# TSOC_MINIPROG_ADAPTER_R1_1.net
KiCad netlist of a schematic drawn in EAGLE
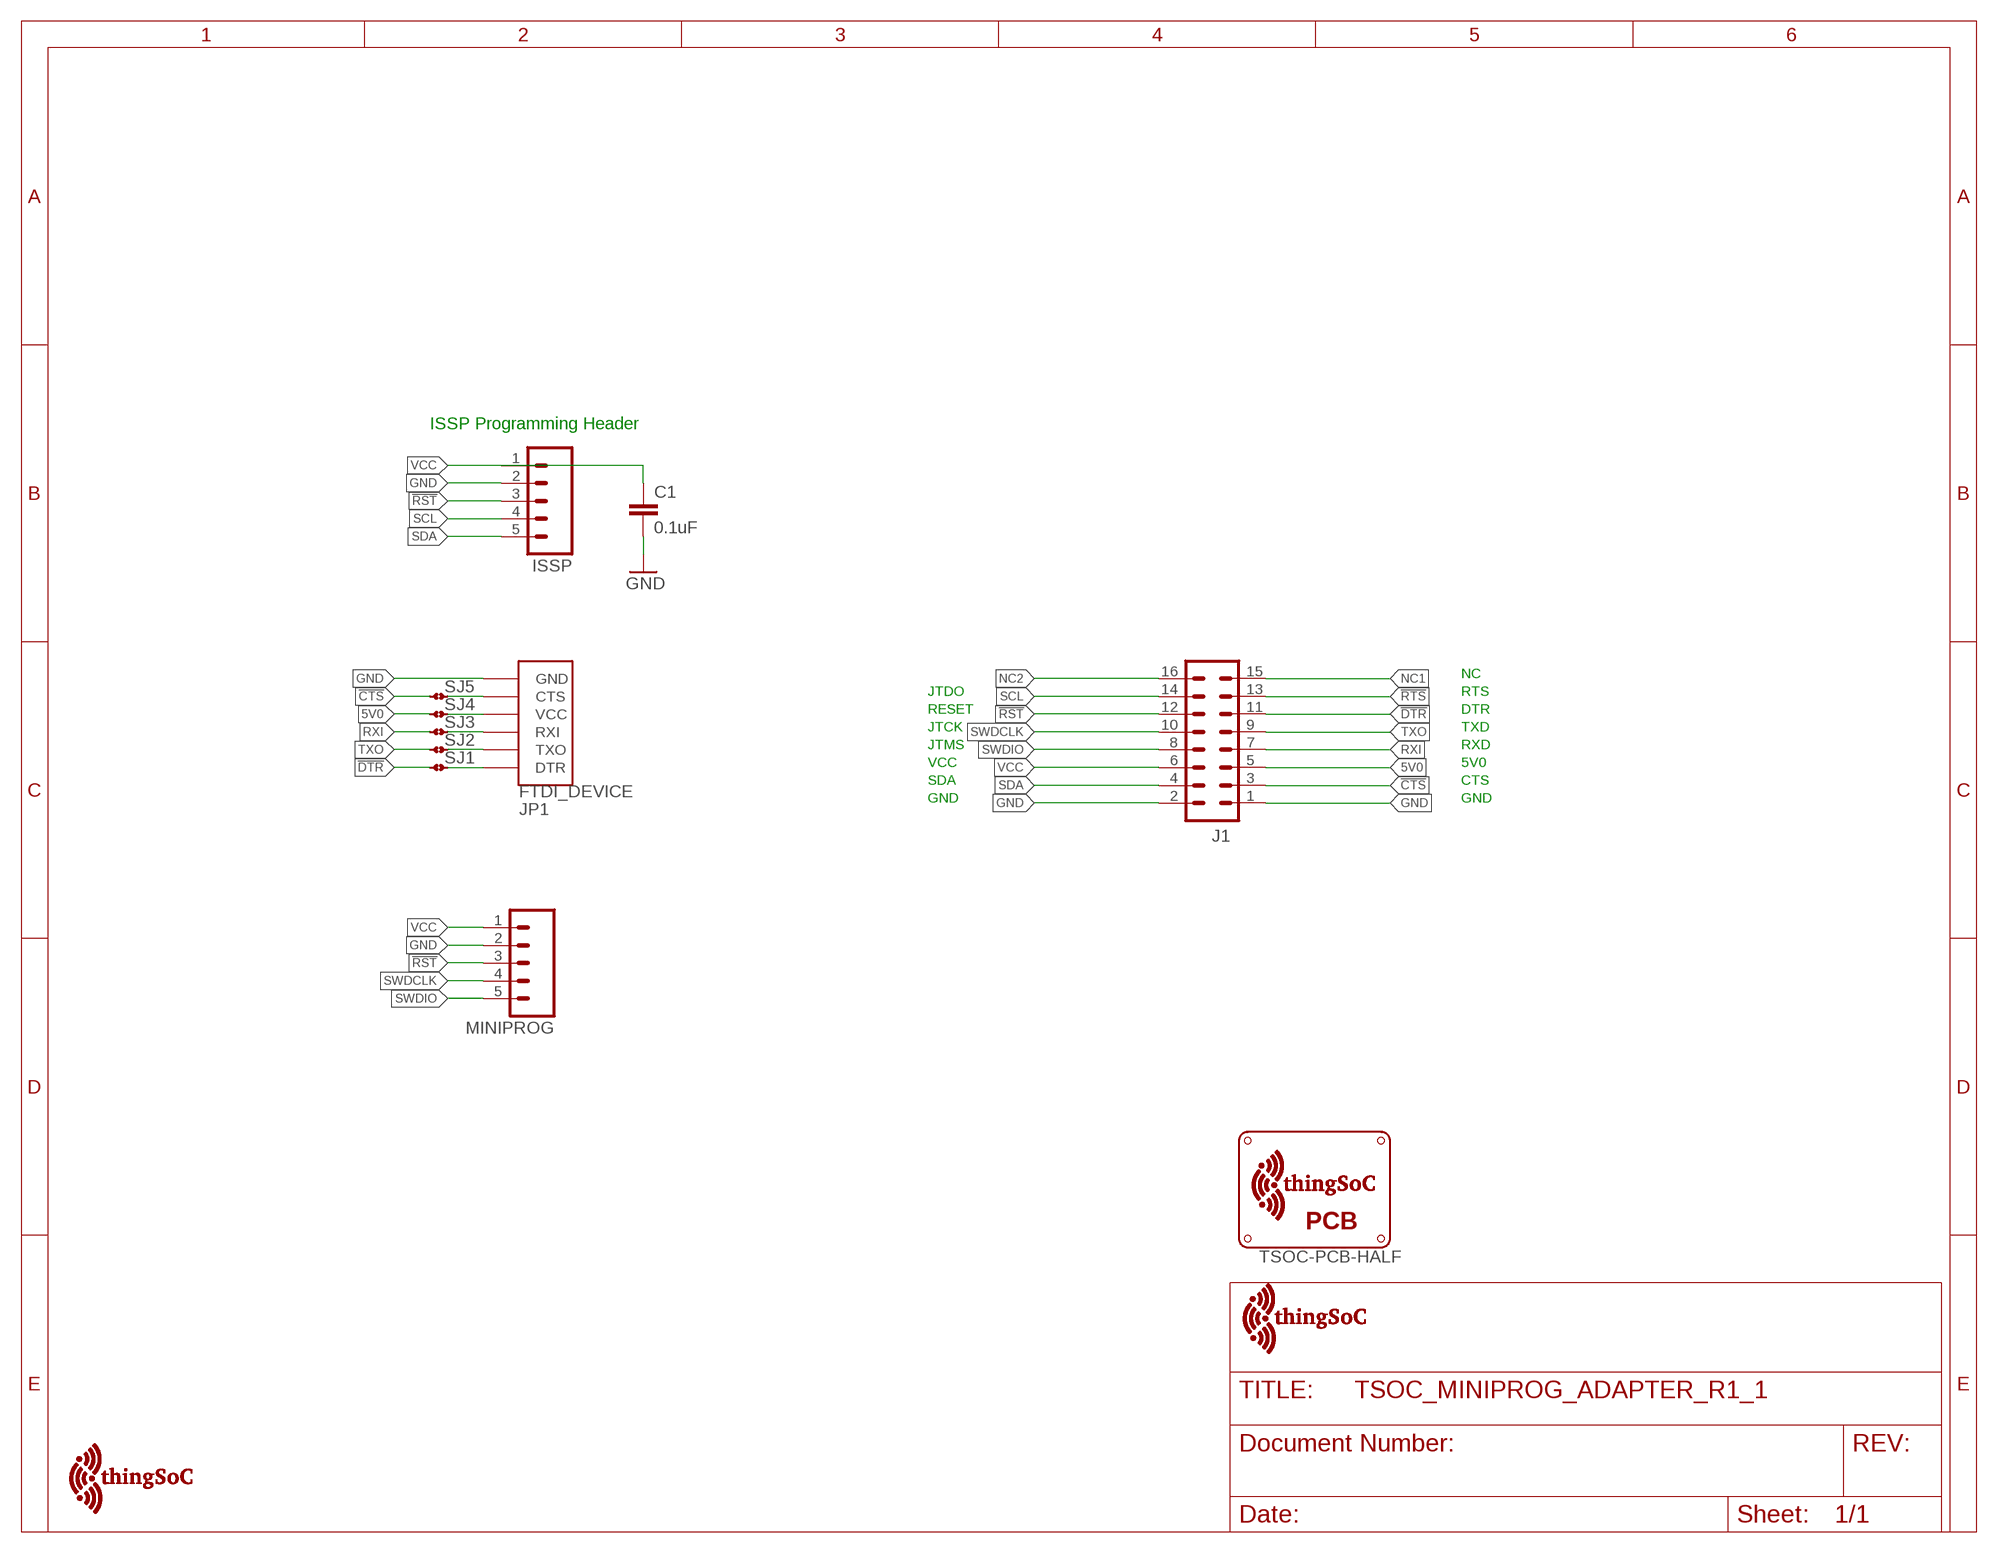
[diagram p0: schematic, sheet 1]

(export (version "E")
  (design (tool "Eeschema 10.0.6"))
  (components
    (comp (ref "C1")
      (value "0.1uF")
      (footprint "eagle-import:0603-CAP")
      (libsource (lib "eagle-import") (part "CAP0603-CAP"))
    )
    (comp (ref "ISSP")
      (value "M05PTH")
      (footprint "eagle-import:1X05")
      (libsource (lib "eagle-import") (part "M05PTH"))
    )
    (comp (ref "J1")
      (value "M08X2")
      (footprint "eagle-import:2X8")
      (libsource (lib "eagle-import") (part "M08X2"))
    )
    (comp (ref "JP1")
      (value "FTDI_DEVICE")
      (footprint "eagle-import:FTDI_DEVICE_SIDE")
      (libsource (lib "eagle-import") (part "FTDI_DEVICE"))
    )
    (comp (ref "MINIPROG")
      (value "M05PTH")
      (footprint "eagle-import:1X05")
      (libsource (lib "eagle-import") (part "SparkFun-Connectors_M05PTH"))
    )
    (comp (ref "SJ1")
      (value "JMP-2-NO")
      (footprint "eagle-import:JMP-2-NO")
      (libsource (lib "eagle-import") (part "JMP-2-NO"))
    )
    (comp (ref "SJ2")
      (value "JMP-2-NO")
      (footprint "eagle-import:JMP-2-NO")
      (libsource (lib "eagle-import") (part "JMP-2-NO"))
    )
    (comp (ref "SJ3")
      (value "JMP-2-NO")
      (footprint "eagle-import:JMP-2-NO")
      (libsource (lib "eagle-import") (part "JMP-2-NO"))
    )
    (comp (ref "SJ4")
      (value "JMP-2-NO")
      (footprint "eagle-import:JMP-2-NO")
      (libsource (lib "eagle-import") (part "JMP-2-NO"))
    )
    (comp (ref "SJ5")
      (value "JMP-2-NO")
      (footprint "eagle-import:JMP-2-NO")
      (libsource (lib "eagle-import") (part "JMP-2-NO"))
    )
    (comp (ref "U$3")
      (value "TSOC-LOGO-SMALL")
      (footprint "eagle-import:TSOC-LOGO-SML")
      (libsource (lib "eagle-import") (part "TSOC-LOGO-SMALL"))
    )
    (comp (ref "U$4")
      (value "TSOC-PCB-HALF")
      (footprint "eagle-import:TSOC-BB-BRD-HALF")
      (libsource (lib "eagle-import") (part "TSOC-PCB-HALF"))
    )
    (comp (ref "U$5")
      (value "TSOC-LOGO-SMALL")
      (footprint "eagle-import:TSOC-LOGO-SML")
      (libsource (lib "eagle-import") (part "TSOC-LOGO-SMALL"))
    )
    (comp (ref "U$6")
      (value "TSOC-LOGO-LRG")
      (footprint "eagle-import:TSOC-LOGO-LRG")
      (libsource (lib "eagle-import") (part "TSOC-LOGO-LRG"))
    )
  )
  (nets
    (net (code "1") (name "/~{CTS}") (class "Default")
      (node (ref "J1") (pin "3") (pinfunction "3_3") (pintype "passive"))
      (node (ref "SJ5") (pin "1") (pinfunction "1_1") (pintype "passive"))
    )
    (net (code "2") (name "/~{DTR}") (class "Default")
      (node (ref "J1") (pin "11") (pinfunction "11_11") (pintype "passive"))
      (node (ref "SJ1") (pin "1") (pinfunction "1_1") (pintype "passive"))
    )
    (net (code "3") (name "/~{RST}") (class "Default")
      (node (ref "ISSP") (pin "3") (pinfunction "3_3") (pintype "passive"))
      (node (ref "J1") (pin "12") (pinfunction "12_12") (pintype "passive"))
      (node (ref "MINIPROG") (pin "3") (pinfunction "3_3") (pintype "passive"))
    )
    (net (code "4") (name "/~{RTS}") (class "Default")
      (node (ref "J1") (pin "13") (pinfunction "13_13") (pintype "passive"))
    )
    (net (code "5") (name "5V0") (class "Default")
      (node (ref "J1") (pin "5") (pinfunction "5_5") (pintype "passive"))
      (node (ref "SJ4") (pin "1") (pinfunction "1_1") (pintype "passive"))
    )
    (net (code "6") (name "GND") (class "Default")
      (node (ref "C1") (pin "2") (pinfunction "2_2") (pintype "passive"))
      (node (ref "ISSP") (pin "2") (pinfunction "2_2") (pintype "passive"))
      (node (ref "J1") (pin "1") (pinfunction "1_1") (pintype "passive"))
      (node (ref "J1") (pin "2") (pinfunction "2_2") (pintype "passive"))
      (node (ref "JP1") (pin "P$6") (pinfunction "GND_P$6") (pintype "bidirectional"))
      (node (ref "MINIPROG") (pin "2") (pinfunction "2_2") (pintype "passive"))
    )
    (net (code "7") (name "NC1") (class "Default")
      (node (ref "J1") (pin "15") (pinfunction "15_15") (pintype "passive"))
    )
    (net (code "8") (name "NC2") (class "Default")
      (node (ref "J1") (pin "16") (pinfunction "16_16") (pintype "passive"))
    )
    (net (code "9") (name "Net-(JP1-CTS)") (class "Default")
      (node (ref "JP1") (pin "P$5") (pinfunction "CTS_P$5") (pintype "bidirectional"))
      (node (ref "SJ5") (pin "2") (pinfunction "2_2") (pintype "passive"))
    )
    (net (code "10") (name "Net-(JP1-DTR)") (class "Default")
      (node (ref "JP1") (pin "P$1") (pinfunction "DTR_P$1") (pintype "bidirectional"))
      (node (ref "SJ1") (pin "2") (pinfunction "2_2") (pintype "passive"))
    )
    (net (code "11") (name "Net-(JP1-RXI)") (class "Default")
      (node (ref "JP1") (pin "P$3") (pinfunction "RXI_P$3") (pintype "bidirectional"))
      (node (ref "SJ3") (pin "2") (pinfunction "2_2") (pintype "passive"))
    )
    (net (code "12") (name "Net-(JP1-TXO)") (class "Default")
      (node (ref "JP1") (pin "P$2") (pinfunction "TXO_P$2") (pintype "bidirectional"))
      (node (ref "SJ2") (pin "2") (pinfunction "2_2") (pintype "passive"))
    )
    (net (code "13") (name "Net-(JP1-VCC)") (class "Default")
      (node (ref "JP1") (pin "P$4") (pinfunction "VCC_P$4") (pintype "bidirectional"))
      (node (ref "SJ4") (pin "2") (pinfunction "2_2") (pintype "passive"))
    )
    (net (code "14") (name "RXI") (class "Default")
      (node (ref "J1") (pin "7") (pinfunction "7_7") (pintype "passive"))
      (node (ref "SJ3") (pin "1") (pinfunction "1_1") (pintype "passive"))
    )
    (net (code "15") (name "SCL") (class "Default")
      (node (ref "ISSP") (pin "4") (pinfunction "4_4") (pintype "passive"))
      (node (ref "J1") (pin "14") (pinfunction "14_14") (pintype "passive"))
    )
    (net (code "16") (name "SDA") (class "Default")
      (node (ref "ISSP") (pin "5") (pinfunction "5_5") (pintype "passive"))
      (node (ref "J1") (pin "4") (pinfunction "4_4") (pintype "passive"))
    )
    (net (code "17") (name "SWDCLK") (class "Default")
      (node (ref "J1") (pin "10") (pinfunction "10_10") (pintype "passive"))
      (node (ref "MINIPROG") (pin "4") (pinfunction "4_4") (pintype "passive"))
    )
    (net (code "18") (name "SWDIO") (class "Default")
      (node (ref "J1") (pin "8") (pinfunction "8_8") (pintype "passive"))
      (node (ref "MINIPROG") (pin "5") (pinfunction "5_5") (pintype "passive"))
    )
    (net (code "19") (name "TXO") (class "Default")
      (node (ref "J1") (pin "9") (pinfunction "9_9") (pintype "passive"))
      (node (ref "SJ2") (pin "1") (pinfunction "1_1") (pintype "passive"))
    )
    (net (code "20") (name "VCC") (class "Default")
      (node (ref "C1") (pin "1") (pinfunction "1_1") (pintype "passive"))
      (node (ref "ISSP") (pin "1") (pinfunction "1_1") (pintype "passive"))
      (node (ref "J1") (pin "6") (pinfunction "6_6") (pintype "passive"))
      (node (ref "MINIPROG") (pin "1") (pinfunction "1_1") (pintype "passive"))
    )
  )
)
